# Clock_management.net
KiCad netlist of a schematic drawn in Altium Designer
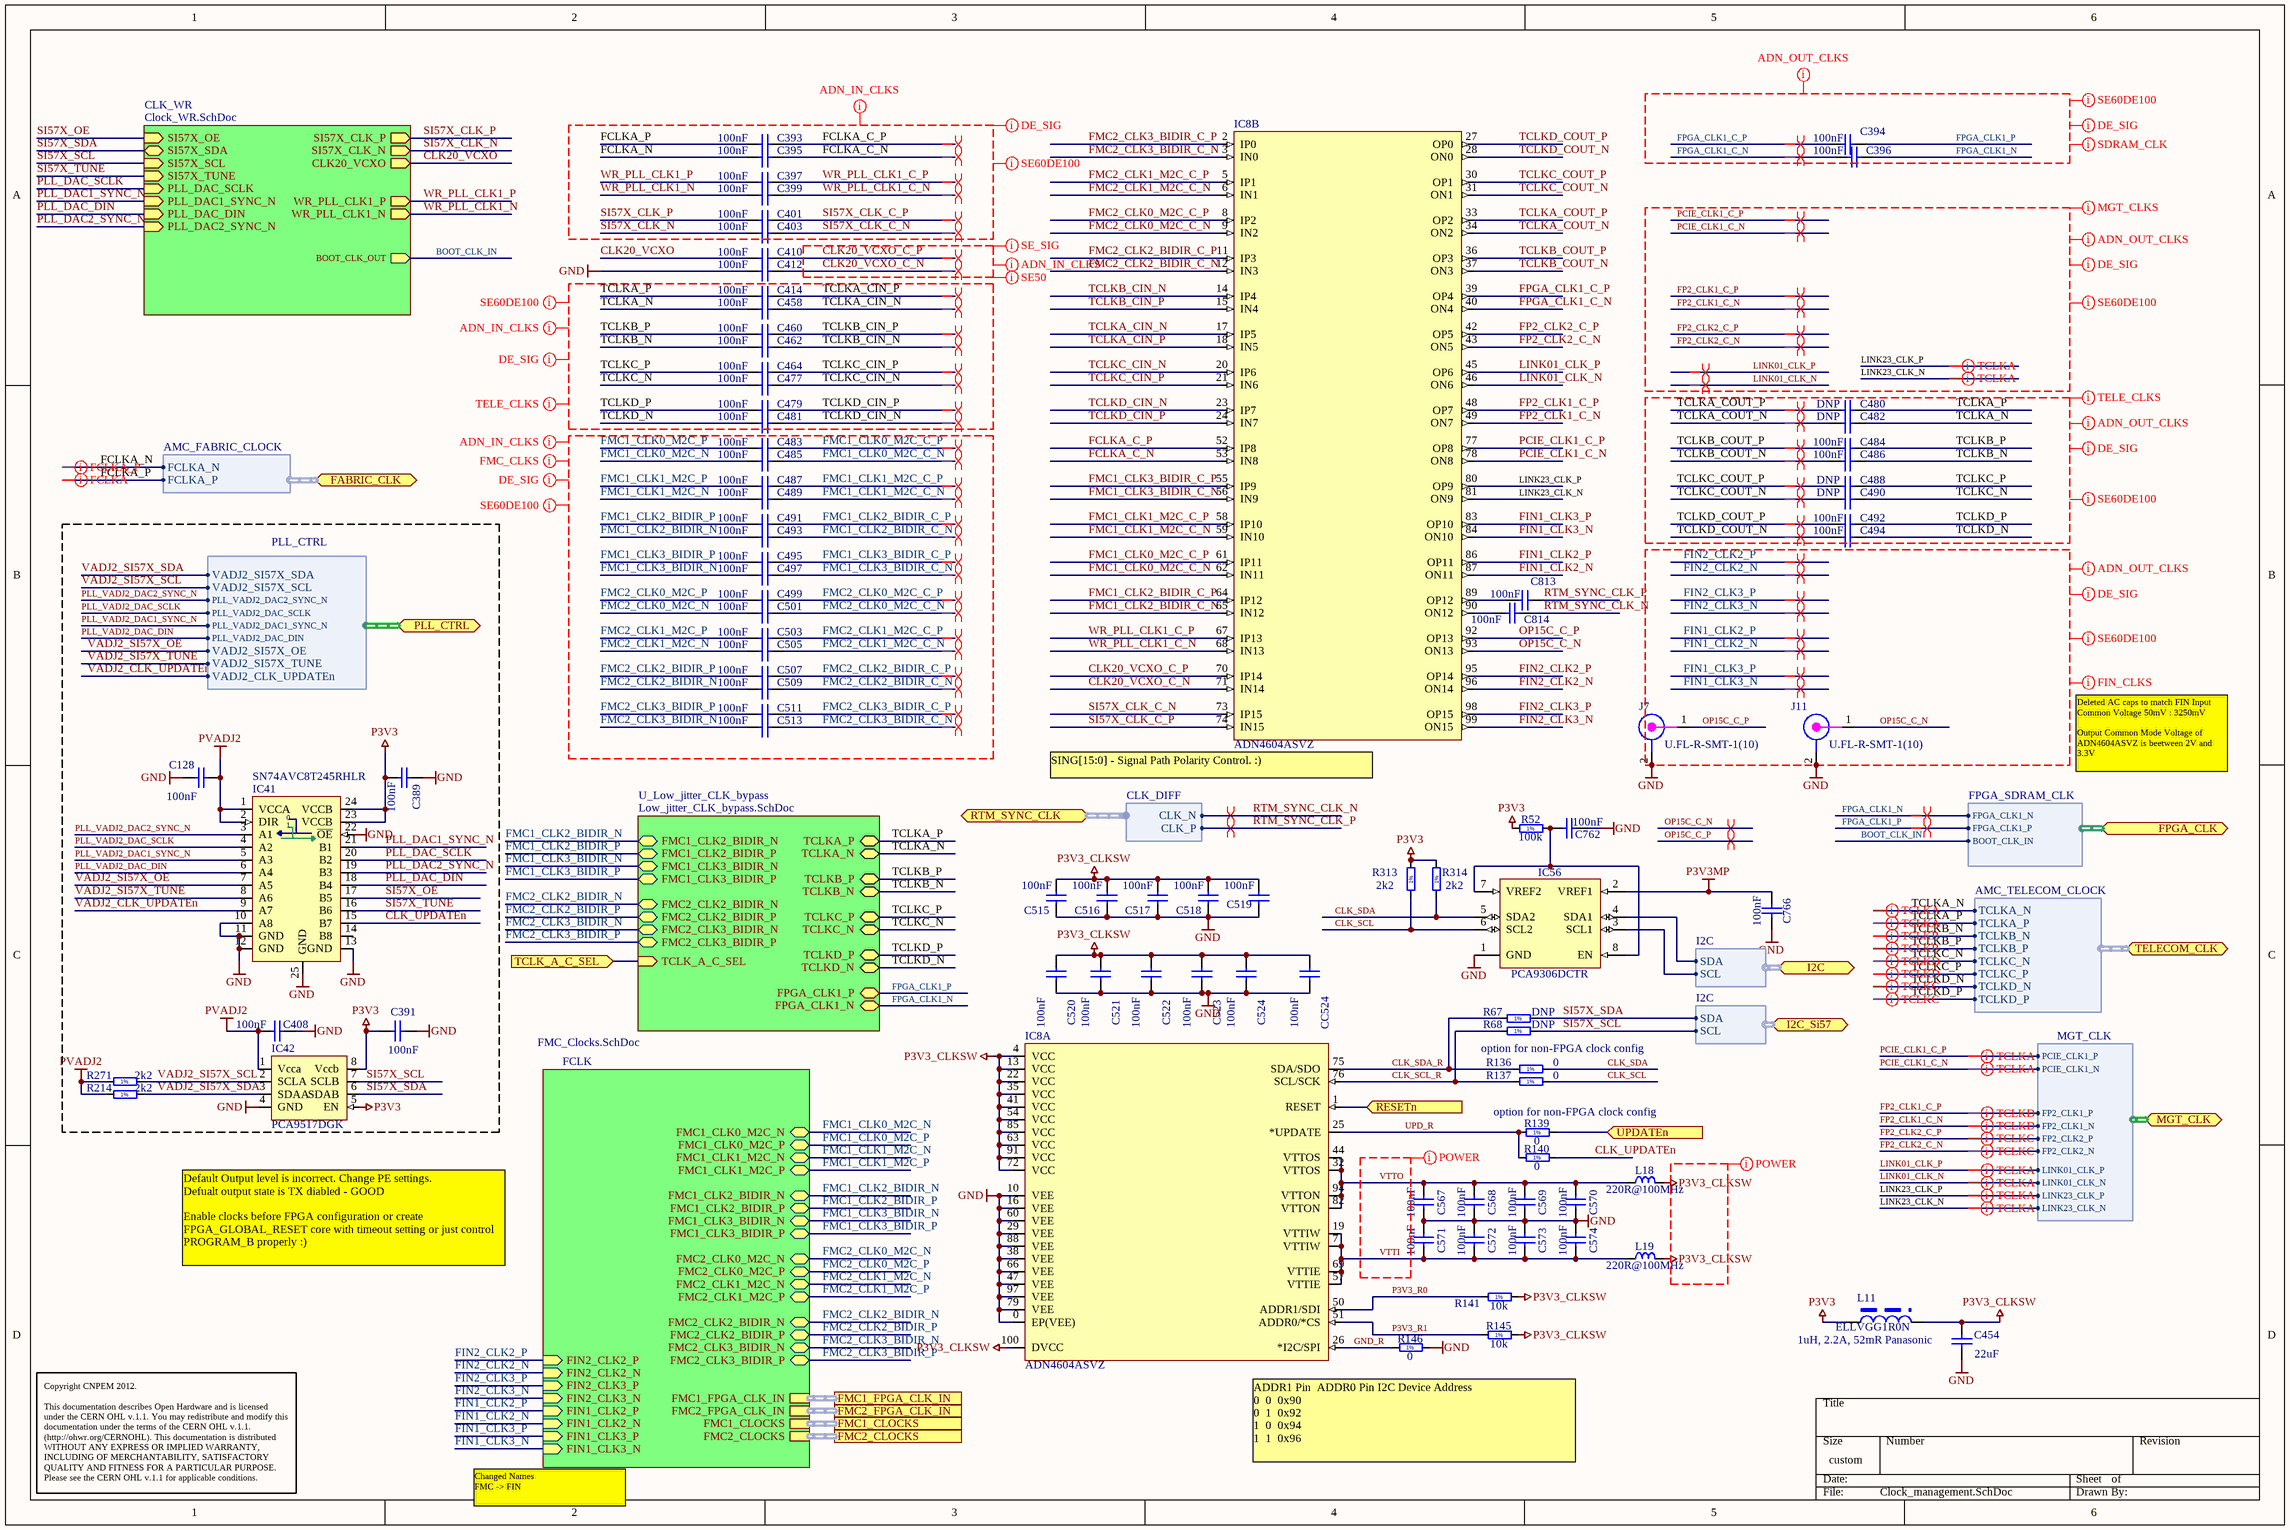
[diagram p0: Clock_management.SchDoc]

(export (version "E")
  (design (tool "Eeschema 10.0.6"))
  (components
    (comp (ref "C128")
      (value "100nF")
      (footprint "CAPC0603X33N")
      (description "Non-polarised capacitor")
      (fields
        (field (name "PART NUMBER") "CC0201_100NF_6.3V_10%_X5R")
        (field (name "VOLTAGE") "6.3V")
        (field (name "AUTHOR") "CERN DEM JLC")
      )
      (libsource (lib "Capacitors") (part "Capacitor - non polarized"))
    )
    (comp (ref "C389")
      (value "100nF")
      (footprint "CAPC0603X33N")
      (description "Non-polarised capacitor")
      (fields
        (field (name "PART NUMBER") "CC0201_100NF_6.3V_10%_X5R")
        (field (name "VOLTAGE") "6.3V")
        (field (name "AUTHOR") "CERN DEM JLC")
      )
      (libsource (lib "Capacitors") (part "Capacitor - non polarized"))
    )
    (comp (ref "C391")
      (value "100nF")
      (footprint "CAPC0603X33N")
      (description "Non-polarised capacitor")
      (fields
        (field (name "PART NUMBER") "CC0201_100NF_6.3V_10%_X5R")
        (field (name "VOLTAGE") "6.3V")
        (field (name "AUTHOR") "CERN DEM JLC")
      )
      (libsource (lib "Capacitors") (part "Capacitor - non polarized"))
    )
    (comp (ref "C393")
      (value "100nF")
      (footprint "CAPC0603X33N")
      (description "Non-polarised capacitor")
      (fields
        (field (name "PART NUMBER") "CC0201_100NF_6.3V_10%_X5R")
        (field (name "VOLTAGE") "6.3V")
        (field (name "AUTHOR") "CERN DEM JLC")
      )
      (libsource (lib "Capacitors") (part "Capacitor - non polarized"))
    )
    (comp (ref "C394")
      (value "100nF")
      (footprint "CAPC0603X33N")
      (description "Non-polarised capacitor")
      (fields
        (field (name "PART NUMBER") "CC0201_100NF_6.3V_10%_X5R")
        (field (name "VOLTAGE") "6.3V")
        (field (name "AUTHOR") "CERN DEM JLC")
      )
      (libsource (lib "Capacitors") (part "Capacitor - non polarized"))
    )
    (comp (ref "C395")
      (value "100nF")
      (footprint "CAPC0603X33N")
      (description "Non-polarised capacitor")
      (fields
        (field (name "PART NUMBER") "CC0201_100NF_6.3V_10%_X5R")
        (field (name "VOLTAGE") "6.3V")
        (field (name "AUTHOR") "CERN DEM JLC")
      )
      (libsource (lib "Capacitors") (part "Capacitor - non polarized"))
    )
    (comp (ref "C396")
      (value "100nF")
      (footprint "CAPC0603X33N")
      (description "Non-polarised capacitor")
      (fields
        (field (name "PART NUMBER") "CC0201_100NF_6.3V_10%_X5R")
        (field (name "VOLTAGE") "6.3V")
        (field (name "AUTHOR") "CERN DEM JLC")
      )
      (libsource (lib "Capacitors") (part "Capacitor - non polarized"))
    )
    (comp (ref "C397")
      (value "100nF")
      (footprint "CAPC0603X33N")
      (description "Non-polarised capacitor")
      (fields
        (field (name "PART NUMBER") "CC0201_100NF_6.3V_10%_X5R")
        (field (name "VOLTAGE") "6.3V")
        (field (name "AUTHOR") "CERN DEM JLC")
      )
      (libsource (lib "Capacitors") (part "Capacitor - non polarized"))
    )
    (comp (ref "C399")
      (value "100nF")
      (footprint "CAPC0603X33N")
      (description "Non-polarised capacitor")
      (fields
        (field (name "PART NUMBER") "CC0201_100NF_6.3V_10%_X5R")
        (field (name "VOLTAGE") "6.3V")
        (field (name "AUTHOR") "CERN DEM JLC")
      )
      (libsource (lib "Capacitors") (part "Capacitor - non polarized"))
    )
    (comp (ref "C401")
      (value "100nF")
      (footprint "CAPC0603X33N")
      (description "Non-polarised capacitor")
      (fields
        (field (name "PART NUMBER") "CC0201_100NF_6.3V_10%_X5R")
        (field (name "VOLTAGE") "6.3V")
        (field (name "AUTHOR") "CERN DEM JLC")
      )
      (libsource (lib "Capacitors") (part "Capacitor - non polarized"))
    )
    (comp (ref "C403")
      (value "100nF")
      (footprint "CAPC0603X33N")
      (description "Non-polarised capacitor")
      (fields
        (field (name "PART NUMBER") "CC0201_100NF_6.3V_10%_X5R")
        (field (name "VOLTAGE") "6.3V")
        (field (name "AUTHOR") "CERN DEM JLC")
      )
      (libsource (lib "Capacitors") (part "Capacitor - non polarized"))
    )
    (comp (ref "C408")
      (value "100nF")
      (footprint "CAPC0603X33N")
      (description "Non-polarised capacitor")
      (fields
        (field (name "PART NUMBER") "CC0201_100NF_6.3V_10%_X5R")
        (field (name "VOLTAGE") "6.3V")
        (field (name "AUTHOR") "CERN DEM JLC")
      )
      (libsource (lib "Capacitors") (part "Capacitor - non polarized"))
    )
    (comp (ref "C410")
      (value "100nF")
      (footprint "CAPC0603X33N")
      (description "Non-polarised capacitor")
      (fields
        (field (name "PART NUMBER") "CC0201_100NF_6.3V_10%_X5R")
        (field (name "VOLTAGE") "6.3V")
        (field (name "AUTHOR") "CERN DEM JLC")
      )
      (libsource (lib "Capacitors") (part "Capacitor - non polarized"))
    )
    (comp (ref "C412")
      (value "100nF")
      (footprint "CAPC0603X33N")
      (description "Non-polarised capacitor")
      (fields
        (field (name "PART NUMBER") "CC0201_100NF_6.3V_10%_X5R")
        (field (name "VOLTAGE") "6.3V")
        (field (name "AUTHOR") "CERN DEM JLC")
      )
      (libsource (lib "Capacitors") (part "Capacitor - non polarized"))
    )
    (comp (ref "C414")
      (value "100nF")
      (footprint "CAPC0603X33N")
      (description "Non-polarised capacitor")
      (fields
        (field (name "PART NUMBER") "CC0201_100NF_6.3V_10%_X5R")
        (field (name "VOLTAGE") "6.3V")
        (field (name "AUTHOR") "CERN DEM JLC")
      )
      (libsource (lib "Capacitors") (part "Capacitor - non polarized"))
    )
    (comp (ref "C454")
      (value "22uF")
      (footprint "CAPC3216X180N")
      (description "Non-polarised capacitor")
      (fields
        (field (name "PART NUMBER") "CC1206_22UF_10V_10%_X7R")
        (field (name "VOLTAGE") "10V")
        (field (name "AUTHOR") "CERN DEM JLC")
      )
      (libsource (lib "Capacitors") (part "Capacitor - non polarized"))
    )
    (comp (ref "C458")
      (value "100nF")
      (footprint "CAPC0603X33N")
      (description "Non-polarised capacitor")
      (fields
        (field (name "PART NUMBER") "CC0201_100NF_6.3V_10%_X5R")
        (field (name "VOLTAGE") "6.3V")
        (field (name "AUTHOR") "CERN DEM JLC")
      )
      (libsource (lib "Capacitors") (part "Capacitor - non polarized"))
    )
    (comp (ref "C460")
      (value "100nF")
      (footprint "CAPC0603X33N")
      (description "Non-polarised capacitor")
      (fields
        (field (name "PART NUMBER") "CC0201_100NF_6.3V_10%_X5R")
        (field (name "VOLTAGE") "6.3V")
        (field (name "AUTHOR") "CERN DEM JLC")
      )
      (libsource (lib "Capacitors") (part "Capacitor - non polarized"))
    )
    (comp (ref "C462")
      (value "100nF")
      (footprint "CAPC0603X33N")
      (description "Non-polarised capacitor")
      (fields
        (field (name "PART NUMBER") "CC0201_100NF_6.3V_10%_X5R")
        (field (name "VOLTAGE") "6.3V")
        (field (name "AUTHOR") "CERN DEM JLC")
      )
      (libsource (lib "Capacitors") (part "Capacitor - non polarized"))
    )
    (comp (ref "C464")
      (value "100nF")
      (footprint "CAPC0603X33N")
      (description "Non-polarised capacitor")
      (fields
        (field (name "PART NUMBER") "CC0201_100NF_6.3V_10%_X5R")
        (field (name "VOLTAGE") "6.3V")
        (field (name "AUTHOR") "CERN DEM JLC")
      )
      (libsource (lib "Capacitors") (part "Capacitor - non polarized"))
    )
    (comp (ref "C477")
      (value "100nF")
      (footprint "CAPC0603X33N")
      (description "Non-polarised capacitor")
      (fields
        (field (name "PART NUMBER") "CC0201_100NF_6.3V_10%_X5R")
        (field (name "VOLTAGE") "6.3V")
        (field (name "AUTHOR") "CERN DEM JLC")
      )
      (libsource (lib "Capacitors") (part "Capacitor - non polarized"))
    )
    (comp (ref "C479")
      (value "100nF")
      (footprint "CAPC0603X33N")
      (description "Non-polarised capacitor")
      (fields
        (field (name "PART NUMBER") "CC0201_100NF_6.3V_10%_X5R")
        (field (name "VOLTAGE") "6.3V")
        (field (name "AUTHOR") "CERN DEM JLC")
      )
      (libsource (lib "Capacitors") (part "Capacitor - non polarized"))
    )
    (comp (ref "C480")
      (value "DNP")
      (footprint "CAPC0603X33N")
      (description "Non-polarised capacitor")
      (fields
        (field (name "PART NUMBER") "CC0201_100NF_6.3V_10%_X5R")
        (field (name "VOLTAGE") "6.3V")
        (field (name "AUTHOR") "CERN DEM JLC")
      )
      (libsource (lib "Capacitors") (part "Capacitor - non polarized"))
    )
    (comp (ref "C481")
      (value "100nF")
      (footprint "CAPC0603X33N")
      (description "Non-polarised capacitor")
      (fields
        (field (name "PART NUMBER") "CC0201_100NF_6.3V_10%_X5R")
        (field (name "VOLTAGE") "6.3V")
        (field (name "AUTHOR") "CERN DEM JLC")
      )
      (libsource (lib "Capacitors") (part "Capacitor - non polarized"))
    )
    (comp (ref "C482")
      (value "DNP")
      (footprint "CAPC0603X33N")
      (description "Non-polarised capacitor")
      (fields
        (field (name "PART NUMBER") "CC0201_100NF_6.3V_10%_X5R")
        (field (name "VOLTAGE") "6.3V")
        (field (name "AUTHOR") "CERN DEM JLC")
      )
      (libsource (lib "Capacitors") (part "Capacitor - non polarized"))
    )
    (comp (ref "C483")
      (value "100nF")
      (footprint "CAPC0603X33N")
      (description "Non-polarised capacitor")
      (fields
        (field (name "PART NUMBER") "CC0201_100NF_6.3V_10%_X5R")
        (field (name "VOLTAGE") "6.3V")
        (field (name "AUTHOR") "CERN DEM JLC")
      )
      (libsource (lib "Capacitors") (part "Capacitor - non polarized"))
    )
    (comp (ref "C484")
      (value "100nF")
      (footprint "CAPC0603X33N")
      (description "Non-polarised capacitor")
      (fields
        (field (name "PART NUMBER") "CC0201_100NF_6.3V_10%_X5R")
        (field (name "VOLTAGE") "6.3V")
        (field (name "AUTHOR") "CERN DEM JLC")
      )
      (libsource (lib "Capacitors") (part "Capacitor - non polarized"))
    )
    (comp (ref "C485")
      (value "100nF")
      (footprint "CAPC0603X33N")
      (description "Non-polarised capacitor")
      (fields
        (field (name "PART NUMBER") "CC0201_100NF_6.3V_10%_X5R")
        (field (name "VOLTAGE") "6.3V")
        (field (name "AUTHOR") "CERN DEM JLC")
      )
      (libsource (lib "Capacitors") (part "Capacitor - non polarized"))
    )
    (comp (ref "C486")
      (value "100nF")
      (footprint "CAPC0603X33N")
      (description "Non-polarised capacitor")
      (fields
        (field (name "PART NUMBER") "CC0201_100NF_6.3V_10%_X5R")
        (field (name "VOLTAGE") "6.3V")
        (field (name "AUTHOR") "CERN DEM JLC")
      )
      (libsource (lib "Capacitors") (part "Capacitor - non polarized"))
    )
    (comp (ref "C487")
      (value "100nF")
      (footprint "CAPC0603X33N")
      (description "Non-polarised capacitor")
      (fields
        (field (name "PART NUMBER") "CC0201_100NF_6.3V_10%_X5R")
        (field (name "VOLTAGE") "6.3V")
        (field (name "AUTHOR") "CERN DEM JLC")
      )
      (libsource (lib "Capacitors") (part "Capacitor - non polarized"))
    )
    (comp (ref "C488")
      (value "DNP")
      (footprint "CAPC0603X33N")
      (description "Non-polarised capacitor")
      (fields
        (field (name "PART NUMBER") "CC0201_100NF_6.3V_10%_X5R")
        (field (name "VOLTAGE") "6.3V")
        (field (name "AUTHOR") "CERN DEM JLC")
      )
      (libsource (lib "Capacitors") (part "Capacitor - non polarized"))
    )
    (comp (ref "C489")
      (value "100nF")
      (footprint "CAPC0603X33N")
      (description "Non-polarised capacitor")
      (fields
        (field (name "PART NUMBER") "CC0201_100NF_6.3V_10%_X5R")
        (field (name "VOLTAGE") "6.3V")
        (field (name "AUTHOR") "CERN DEM JLC")
      )
      (libsource (lib "Capacitors") (part "Capacitor - non polarized"))
    )
    (comp (ref "C490")
      (value "DNP")
      (footprint "CAPC0603X33N")
      (description "Non-polarised capacitor")
      (fields
        (field (name "PART NUMBER") "CC0201_100NF_6.3V_10%_X5R")
        (field (name "VOLTAGE") "6.3V")
        (field (name "AUTHOR") "CERN DEM JLC")
      )
      (libsource (lib "Capacitors") (part "Capacitor - non polarized"))
    )
    (comp (ref "C491")
      (value "100nF")
      (footprint "CAPC0603X33N")
      (description "Non-polarised capacitor")
      (fields
        (field (name "PART NUMBER") "CC0201_100NF_6.3V_10%_X5R")
        (field (name "VOLTAGE") "6.3V")
        (field (name "AUTHOR") "CERN DEM JLC")
      )
      (libsource (lib "Capacitors") (part "Capacitor - non polarized"))
    )
    (comp (ref "C492")
      (value "100nF")
      (footprint "CAPC0603X33N")
      (description "Non-polarised capacitor")
      (fields
        (field (name "PART NUMBER") "CC0201_100NF_6.3V_10%_X5R")
        (field (name "VOLTAGE") "6.3V")
        (field (name "AUTHOR") "CERN DEM JLC")
      )
      (libsource (lib "Capacitors") (part "Capacitor - non polarized"))
    )
    (comp (ref "C493")
      (value "100nF")
      (footprint "CAPC0603X33N")
      (description "Non-polarised capacitor")
      (fields
        (field (name "PART NUMBER") "CC0201_100NF_6.3V_10%_X5R")
        (field (name "VOLTAGE") "6.3V")
        (field (name "AUTHOR") "CERN DEM JLC")
      )
      (libsource (lib "Capacitors") (part "Capacitor - non polarized"))
    )
    (comp (ref "C494")
      (value "100nF")
      (footprint "CAPC0603X33N")
      (description "Non-polarised capacitor")
      (fields
        (field (name "PART NUMBER") "CC0201_100NF_6.3V_10%_X5R")
        (field (name "VOLTAGE") "6.3V")
        (field (name "AUTHOR") "CERN DEM JLC")
      )
      (libsource (lib "Capacitors") (part "Capacitor - non polarized"))
    )
    (comp (ref "C495")
      (value "100nF")
      (footprint "CAPC0603X33N")
      (description "Non-polarised capacitor")
      (fields
        (field (name "PART NUMBER") "CC0201_100NF_6.3V_10%_X5R")
        (field (name "VOLTAGE") "6.3V")
        (field (name "AUTHOR") "CERN DEM JLC")
      )
      (libsource (lib "Capacitors") (part "Capacitor - non polarized"))
    )
    (comp (ref "C497")
      (value "100nF")
      (footprint "CAPC0603X33N")
      (description "Non-polarised capacitor")
      (fields
        (field (name "PART NUMBER") "CC0201_100NF_6.3V_10%_X5R")
        (field (name "VOLTAGE") "6.3V")
        (field (name "AUTHOR") "CERN DEM JLC")
      )
      (libsource (lib "Capacitors") (part "Capacitor - non polarized"))
    )
    (comp (ref "C499")
      (value "100nF")
      (footprint "CAPC0603X33N")
      (description "Non-polarised capacitor")
      (fields
        (field (name "PART NUMBER") "CC0201_100NF_6.3V_10%_X5R")
        (field (name "VOLTAGE") "6.3V")
        (field (name "AUTHOR") "CERN DEM JLC")
      )
      (libsource (lib "Capacitors") (part "Capacitor - non polarized"))
    )
    (comp (ref "C501")
      (value "100nF")
      (footprint "CAPC0603X33N")
      (description "Non-polarised capacitor")
      (fields
        (field (name "PART NUMBER") "CC0201_100NF_6.3V_10%_X5R")
        (field (name "VOLTAGE") "6.3V")
        (field (name "AUTHOR") "CERN DEM JLC")
      )
      (libsource (lib "Capacitors") (part "Capacitor - non polarized"))
    )
    (comp (ref "C503")
      (value "100nF")
      (footprint "CAPC0603X33N")
      (description "Non-polarised capacitor")
      (fields
        (field (name "PART NUMBER") "CC0201_100NF_6.3V_10%_X5R")
        (field (name "VOLTAGE") "6.3V")
        (field (name "AUTHOR") "CERN DEM JLC")
      )
      (libsource (lib "Capacitors") (part "Capacitor - non polarized"))
    )
    (comp (ref "C505")
      (value "100nF")
      (footprint "CAPC0603X33N")
      (description "Non-polarised capacitor")
      (fields
        (field (name "PART NUMBER") "CC0201_100NF_6.3V_10%_X5R")
        (field (name "VOLTAGE") "6.3V")
        (field (name "AUTHOR") "CERN DEM JLC")
      )
      (libsource (lib "Capacitors") (part "Capacitor - non polarized"))
    )
    (comp (ref "C507")
      (value "100nF")
      (footprint "CAPC0603X33N")
      (description "Non-polarised capacitor")
      (fields
        (field (name "PART NUMBER") "CC0201_100NF_6.3V_10%_X5R")
        (field (name "VOLTAGE") "6.3V")
        (field (name "AUTHOR") "CERN DEM JLC")
      )
      (libsource (lib "Capacitors") (part "Capacitor - non polarized"))
    )
    (comp (ref "C509")
      (value "100nF")
      (footprint "CAPC0603X33N")
      (description "Non-polarised capacitor")
      (fields
        (field (name "PART NUMBER") "CC0201_100NF_6.3V_10%_X5R")
        (field (name "VOLTAGE") "6.3V")
        (field (name "AUTHOR") "CERN DEM JLC")
      )
      (libsource (lib "Capacitors") (part "Capacitor - non polarized"))
    )
    (comp (ref "C511")
      (value "100nF")
      (footprint "CAPC0603X33N")
      (description "Non-polarised capacitor")
      (fields
        (field (name "PART NUMBER") "CC0201_100NF_6.3V_10%_X5R")
        (field (name "VOLTAGE") "6.3V")
        (field (name "AUTHOR") "CERN DEM JLC")
      )
      (libsource (lib "Capacitors") (part "Capacitor - non polarized"))
    )
    (comp (ref "C513")
      (value "100nF")
      (footprint "CAPC0603X33N")
      (description "Non-polarised capacitor")
      (fields
        (field (name "PART NUMBER") "CC0201_100NF_6.3V_10%_X5R")
        (field (name "VOLTAGE") "6.3V")
        (field (name "AUTHOR") "CERN DEM JLC")
      )
      (libsource (lib "Capacitors") (part "Capacitor - non polarized"))
    )
    (comp (ref "C515")
      (value "100nF")
      (footprint "CAPC0603X33N")
      (description "Non-polarised capacitor")
      (fields
        (field (name "PART NUMBER") "CC0201_100NF_6.3V_10%_X5R")
        (field (name "VOLTAGE") "6.3V")
        (field (name "AUTHOR") "CERN DEM JLC")
      )
      (libsource (lib "Capacitors") (part "Capacitor - non polarized"))
    )
    (comp (ref "C516")
      (value "100nF")
      (footprint "CAPC0603X33N")
      (description "Non-polarised capacitor")
      (fields
        (field (name "PART NUMBER") "CC0201_100NF_6.3V_10%_X5R")
        (field (name "VOLTAGE") "6.3V")
        (field (name "AUTHOR") "CERN DEM JLC")
      )
      (libsource (lib "Capacitors") (part "Capacitor - non polarized"))
    )
    (comp (ref "C517")
      (value "100nF")
      (footprint "CAPC0603X33N")
      (description "Non-polarised capacitor")
      (fields
        (field (name "PART NUMBER") "CC0201_100NF_6.3V_10%_X5R")
        (field (name "VOLTAGE") "6.3V")
        (field (name "AUTHOR") "CERN DEM JLC")
      )
      (libsource (lib "Capacitors") (part "Capacitor - non polarized"))
    )
    (comp (ref "C518")
      (value "100nF")
      (footprint "CAPC0603X33N")
      (description "Non-polarised capacitor")
      (fields
        (field (name "PART NUMBER") "CC0201_100NF_6.3V_10%_X5R")
        (field (name "VOLTAGE") "6.3V")
        (field (name "AUTHOR") "CERN DEM JLC")
      )
      (libsource (lib "Capacitors") (part "Capacitor - non polarized"))
    )
    (comp (ref "C519")
      (value "100nF")
      (footprint "CAPC0603X33N")
      (description "Non-polarised capacitor")
      (fields
        (field (name "PART NUMBER") "CC0201_100NF_6.3V_10%_X5R")
        (field (name "VOLTAGE") "6.3V")
        (field (name "AUTHOR") "CERN DEM JLC")
      )
      (libsource (lib "Capacitors") (part "Capacitor - non polarized"))
    )
    (comp (ref "C520")
      (value "100nF")
      (footprint "CAPC0603X33N")
      (description "Non-polarised capacitor")
      (fields
        (field (name "PART NUMBER") "CC0201_100NF_6.3V_10%_X5R")
        (field (name "VOLTAGE") "6.3V")
        (field (name "AUTHOR") "CERN DEM JLC")
      )
      (libsource (lib "Capacitors") (part "Capacitor - non polarized"))
    )
    (comp (ref "C521")
      (value "100nF")
      (footprint "CAPC0603X33N")
      (description "Non-polarised capacitor")
      (fields
        (field (name "PART NUMBER") "CC0201_100NF_6.3V_10%_X5R")
        (field (name "VOLTAGE") "6.3V")
        (field (name "AUTHOR") "CERN DEM JLC")
      )
      (libsource (lib "Capacitors") (part "Capacitor - non polarized"))
    )
    (comp (ref "C522")
      (value "100nF")
      (footprint "CAPC0603X33N")
      (description "Non-polarised capacitor")
      (fields
        (field (name "PART NUMBER") "CC0201_100NF_6.3V_10%_X5R")
        (field (name "VOLTAGE") "6.3V")
        (field (name "AUTHOR") "CERN DEM JLC")
      )
      (libsource (lib "Capacitors") (part "Capacitor - non polarized"))
    )
    (comp (ref "C523")
      (value "100nF")
      (footprint "CAPC0603X33N")
      (description "Non-polarised capacitor")
      (fields
        (field (name "PART NUMBER") "CC0201_100NF_6.3V_10%_X5R")
        (field (name "VOLTAGE") "6.3V")
        (field (name "AUTHOR") "CERN DEM JLC")
      )
      (libsource (lib "Capacitors") (part "Capacitor - non polarized"))
    )
    (comp (ref "C524")
      (value "100nF")
      (footprint "CAPC0603X33N")
      (description "Non-polarised capacitor")
      (fields
        (field (name "PART NUMBER") "CC0201_100NF_6.3V_10%_X5R")
        (field (name "VOLTAGE") "6.3V")
        (field (name "AUTHOR") "CERN DEM JLC")
      )
      (libsource (lib "Capacitors") (part "Capacitor - non polarized"))
    )
    (comp (ref "C567")
      (value "100nF")
      (footprint "CAPC0603X33N")
      (description "Non-polarised capacitor")
      (fields
        (field (name "PART NUMBER") "CC0201_100NF_6.3V_10%_X5R")
        (field (name "VOLTAGE") "6.3V")
        (field (name "AUTHOR") "CERN DEM JLC")
      )
      (libsource (lib "Capacitors") (part "Capacitor - non polarized"))
    )
    (comp (ref "C568")
      (value "100nF")
      (footprint "CAPC0603X33N")
      (description "Non-polarised capacitor")
      (fields
        (field (name "PART NUMBER") "CC0201_100NF_6.3V_10%_X5R")
        (field (name "VOLTAGE") "6.3V")
        (field (name "AUTHOR") "CERN DEM JLC")
      )
      (libsource (lib "Capacitors") (part "Capacitor - non polarized"))
    )
    (comp (ref "C569")
      (value "100nF")
      (footprint "CAPC0603X33N")
      (description "Non-polarised capacitor")
      (fields
        (field (name "PART NUMBER") "CC0201_100NF_6.3V_10%_X5R")
        (field (name "VOLTAGE") "6.3V")
        (field (name "AUTHOR") "CERN DEM JLC")
      )
      (libsource (lib "Capacitors") (part "Capacitor - non polarized"))
    )
    (comp (ref "C570")
      (value "100nF")
      (footprint "CAPC0603X33N")
      (description "Non-polarised capacitor")
      (fields
        (field (name "PART NUMBER") "CC0201_100NF_6.3V_10%_X5R")
        (field (name "VOLTAGE") "6.3V")
        (field (name "AUTHOR") "CERN DEM JLC")
      )
      (libsource (lib "Capacitors") (part "Capacitor - non polarized"))
    )
    (comp (ref "C571")
      (value "100nF")
      (footprint "CAPC0603X33N")
      (description "Non-polarised capacitor")
      (fields
        (field (name "PART NUMBER") "CC0201_100NF_6.3V_10%_X5R")
        (field (name "VOLTAGE") "6.3V")
        (field (name "AUTHOR") "CERN DEM JLC")
      )
      (libsource (lib "Capacitors") (part "Capacitor - non polarized"))
    )
    (comp (ref "C572")
      (value "100nF")
      (footprint "CAPC0603X33N")
      (description "Non-polarised capacitor")
      (fields
        (field (name "PART NUMBER") "CC0201_100NF_6.3V_10%_X5R")
        (field (name "VOLTAGE") "6.3V")
        (field (name "AUTHOR") "CERN DEM JLC")
      )
      (libsource (lib "Capacitors") (part "Capacitor - non polarized"))
    )
    (comp (ref "C573")
      (value "100nF")
      (footprint "CAPC0603X33N")
      (description "Non-polarised capacitor")
      (fields
        (field (name "PART NUMBER") "CC0201_100NF_6.3V_10%_X5R")
        (field (name "VOLTAGE") "6.3V")
        (field (name "AUTHOR") "CERN DEM JLC")
      )
      (libsource (lib "Capacitors") (part "Capacitor - non polarized"))
    )
    (comp (ref "C574")
      (value "100nF")
      (footprint "CAPC0603X33N")
      (description "Non-polarised capacitor")
      (fields
        (field (name "PART NUMBER") "CC0201_100NF_6.3V_10%_X5R")
        (field (name "VOLTAGE") "6.3V")
        (field (name "AUTHOR") "CERN DEM JLC")
      )
      (libsource (lib "Capacitors") (part "Capacitor - non polarized"))
    )
    (comp (ref "C762")
      (value "100nF")
      (footprint "CAPC0603X33N")
      (description "Non-polarised capacitor")
      (fields
        (field (name "PART NUMBER") "CC0201_100NF_6.3V_10%_X5R")
        (field (name "VOLTAGE") "6.3V")
        (field (name "AUTHOR") "CERN DEM JLC")
      )
      (libsource (lib "Capacitors") (part "Capacitor - non polarized"))
    )
    (comp (ref "C766")
      (value "100nF")
      (footprint "CAPC0603X33N")
      (description "Non-polarised capacitor")
      (fields
        (field (name "PART NUMBER") "CC0201_100NF_6.3V_10%_X5R")
        (field (name "VOLTAGE") "6.3V")
        (field (name "AUTHOR") "CERN DEM JLC")
      )
      (libsource (lib "Capacitors") (part "Capacitor - non polarized"))
    )
    (comp (ref "C813")
      (value "100nF")
      (footprint "CAPC0603X33N")
      (description "Non-polarised capacitor")
      (fields
        (field (name "PART NUMBER") "CC0201_100NF_6.3V_10%_X5R")
        (field (name "VOLTAGE") "6.3V")
        (field (name "AUTHOR") "CERN DEM JLC")
      )
      (libsource (lib "Capacitors") (part "Capacitor - non polarized"))
    )
    (comp (ref "C814")
      (value "100nF")
      (footprint "CAPC0603X33N")
      (description "Non-polarised capacitor")
      (fields
        (field (name "PART NUMBER") "CC0201_100NF_6.3V_10%_X5R")
        (field (name "VOLTAGE") "6.3V")
        (field (name "AUTHOR") "CERN DEM JLC")
      )
      (libsource (lib "Capacitors") (part "Capacitor - non polarized"))
    )
    (comp (ref "CC524")
      (value "100nF")
      (footprint "CAPC0603X33N")
      (description "Non-polarised capacitor")
      (fields
        (field (name "PART NUMBER") "CC0201_100NF_6.3V_10%_X5R")
        (field (name "VOLTAGE") "6.3V")
        (field (name "AUTHOR") "CERN DEM JLC")
      )
      (libsource (lib "Capacitors") (part "Capacitor - non polarized"))
    )
    (comp (ref "IC8")
      (value "ADN4604ASVZ")
      (footprint "TQFP100_TP")
      (description "16x16 CML crosspoint switch")
      (libsource (lib "LIBRARY_SCH") (part "IFC_ADN4604ASVZ"))
    )
    (comp (ref "IC41")
      (value "SN74AVC8T245RHLR")
      (footprint "QFN50P350X550X100-24N")
      (description "8 channel bidir translator buffer (1.4..3.6V)")
      (libsource (lib "LIBRARY_SCH") (part "74AVC8T245_QFN"))
    )
    (comp (ref "IC42")
      (value "PCA9517DGK")
      (footprint "msop-8")
      (description "LEVEL-TRANSLATING I2C BUS REPEATER")
      (libsource (lib "LIBRARY_SCH") (part "IFC_PCA9517"))
    )
    (comp (ref "IC56")
      (value "PCA9306DCTR")
      (footprint "SOP65P400X130-8N")
      (description "Dual Bidirectional I2C Bus And SMBus Voltage-Level Translator")
      (fields (field (name "MANUFACTURER") "TEXAS INSTRUMENTS") (field (name "AUTHOR") "CERN DEM JLC"))
      (libsource (lib "ICs And Semiconductors") (part "PCA9306DC"))
    )
    (comp (ref "J7")
      (value "U.FL-R-SMT-1(10)")
      (footprint "CON_UFL_HIROSE_RECEPTACLE")
      (description "UFL")
      (libsource (lib "LIBRARY_SCH") (part "CON_UFL_SMD"))
    )
    (comp (ref "J11")
      (value "U.FL-R-SMT-1(10)")
      (footprint "CON_UFL_HIROSE_RECEPTACLE")
      (description "UFL")
      (libsource (lib "LIBRARY_SCH") (part "CON_UFL_SMD"))
    )
    (comp (ref "L11")
      (value "ELLVGG1R0N")
      (footprint "L_ELLVGG2R2N")
      (description "2.2uH, 1.4A, 92mR Panasonic")
      (fields (field (name "ALTIUM_UNNAMED_1") "1uH, 2.2A, 52mR Panasonic"))
      (libsource (lib "LIBRARY_SCH") (part "L_CHOKE_ELLVGG"))
    )
    (comp (ref "L18")
      (value "220R@100MHz")
      (footprint "INDC2012X105N")
      (description "Inductor")
      (fields
        (field (name "PART NUMBER") "IND0805_MURATA_BLM21PG221SN1D")
        (field (name "POWER") "2A")
        (field (name "AUTHOR") "CERN DEM JLC")
      )
      (libsource (lib "Inductors & Transformers") (part "Inductor"))
    )
    (comp (ref "L19")
      (value "220R@100MHz")
      (footprint "INDC2012X105N")
      (description "Inductor")
      (fields
        (field (name "PART NUMBER") "IND0805_MURATA_BLM21PG221SN1D")
        (field (name "POWER") "2A")
        (field (name "AUTHOR") "CERN DEM JLC")
      )
      (libsource (lib "Inductors & Transformers") (part "Inductor"))
    )
    (comp (ref "R52")
      (value "100k")
      (footprint "RESC1005X40N")
      (description "Resistor - 1%")
      (fields
        (field (name "PART NUMBER") "R0402_100K_1%_0.0625W_100PPM")
        (field (name "POWER") "0.0625W")
        (field (name "AUTHOR") "CERN DEM JLC")
      )
      (libsource (lib "Resistors") (part "Resistor - 1%"))
    )
    (comp (ref "R67")
      (value "DNP")
      (footprint "RESC1005X40N")
      (description "Resistor - 1%")
      (fields
        (field (name "PART NUMBER") "R0402_0R_JUMPER")
        (field (name "MANUFACTURER") "GENERIC")
        (field (name "AUTHOR") "CERN DEM JLC")
      )
      (libsource (lib "Resistors") (part "Resistor - 1%"))
    )
    (comp (ref "R68")
      (value "DNP")
      (footprint "RESC1005X40N")
      (description "Resistor - 1%")
      (fields
        (field (name "PART NUMBER") "R0402_0R_JUMPER")
        (field (name "MANUFACTURER") "GENERIC")
        (field (name "AUTHOR") "CERN DEM JLC")
      )
      (libsource (lib "Resistors") (part "Resistor - 1%"))
    )
    (comp (ref "R136")
      (value "0")
      (footprint "RESC1005X40N")
      (description "Resistor - 1%")
      (fields
        (field (name "PART NUMBER") "R0402_0R_JUMPER")
        (field (name "MANUFACTURER") "GENERIC")
        (field (name "AUTHOR") "CERN DEM JLC")
      )
      (libsource (lib "Resistors") (part "Resistor - 1%"))
    )
    (comp (ref "R137")
      (value "0")
      (footprint "RESC1005X40N")
      (description "Resistor - 1%")
      (fields
        (field (name "PART NUMBER") "R0402_0R_JUMPER")
        (field (name "MANUFACTURER") "GENERIC")
        (field (name "AUTHOR") "CERN DEM JLC")
      )
      (libsource (lib "Resistors") (part "Resistor - 1%"))
    )
    (comp (ref "R139")
      (value "0")
      (footprint "RESC1005X40N")
      (description "Resistor - 1%")
      (fields
        (field (name "PART NUMBER") "R0402_0R_JUMPER")
        (field (name "MANUFACTURER") "GENERIC")
        (field (name "AUTHOR") "CERN DEM JLC")
      )
      (libsource (lib "Resistors") (part "Resistor - 1%"))
    )
    (comp (ref "R140")
      (value "0")
      (footprint "RESC1005X40N")
      (description "Resistor - 1%")
      (fields
        (field (name "PART NUMBER") "R0402_0R_JUMPER")
        (field (name "MANUFACTURER") "GENERIC")
        (field (name "AUTHOR") "CERN DEM JLC")
      )
      (libsource (lib "Resistors") (part "Resistor - 1%"))
    )
    (comp (ref "R141")
      (value "10k")
      (footprint "RESC1005X40N")
      (description "Resistor - 1%")
      (fields
        (field (name "PART NUMBER") "R0402_10K_1%_0.0625W_100PPM")
        (field (name "POWER") "0.0625W")
        (field (name "AUTHOR") "CERN DEM JLC")
      )
      (libsource (lib "Resistors") (part "Resistor - 1%"))
    )
    (comp (ref "R145")
      (value "10k")
      (footprint "RESC1005X40N")
      (description "Resistor - 1%")
      (fields
        (field (name "PART NUMBER") "R0402_10K_1%_0.0625W_100PPM")
        (field (name "POWER") "0.0625W")
        (field (name "AUTHOR") "CERN DEM JLC")
      )
      (libsource (lib "Resistors") (part "Resistor - 1%"))
    )
    (comp (ref "R146")
      (value "0")
      (footprint "RESC1005X40N")
      (description "Resistor - 1%")
      (fields
        (field (name "PART NUMBER") "R0402_0R_JUMPER")
        (field (name "MANUFACTURER") "GENERIC")
        (field (name "AUTHOR") "CERN DEM JLC")
      )
      (libsource (lib "Resistors") (part "Resistor - 1%"))
    )
    (comp (ref "R214")
      (value "2k2")
      (footprint "RESC1005X40N")
      (description "Resistor - 1%")
      (fields
        (field (name "PART NUMBER") "R0402_2K2_1%_0.0625W_100PPM")
        (field (name "POWER") "0.0625W")
        (field (name "AUTHOR") "CERN DEM JLC")
      )
      (libsource (lib "Resistors") (part "Resistor - 1%"))
    )
    (comp (ref "R271")
      (value "2k2")
      (footprint "RESC1005X40N")
      (description "Resistor - 1%")
      (fields
        (field (name "PART NUMBER") "R0402_2K2_1%_0.0625W_100PPM")
        (field (name "POWER") "0.0625W")
        (field (name "AUTHOR") "CERN DEM JLC")
      )
      (libsource (lib "Resistors") (part "Resistor - 1%"))
    )
    (comp (ref "R313")
      (value "2k2")
      (footprint "RESC1005X40N")
      (description "Resistor - 1%")
      (fields
        (field (name "PART NUMBER") "R0402_2K2_1%_0.0625W_100PPM")
        (field (name "POWER") "0.0625W")
        (field (name "AUTHOR") "CERN DEM JLC")
      )
      (libsource (lib "Resistors") (part "Resistor - 1%"))
    )
    (comp (ref "R314")
      (value "2k2")
      (footprint "RESC1005X40N")
      (description "Resistor - 1%")
      (fields
        (field (name "PART NUMBER") "R0402_2K2_1%_0.0625W_100PPM")
        (field (name "POWER") "0.0625W")
        (field (name "AUTHOR") "CERN DEM JLC")
      )
      (libsource (lib "Resistors") (part "Resistor - 1%"))
    )
  )
  (nets
    (net (code "13") (name "/CLK20_VCXO") (class "Default")
      (node (ref "C410") (pin "1") (pinfunction "1_1") (pintype "passive"))
    )
    (net (code "14") (name "/CLK20_VCXO_C_N") (class "Default")
      (node (ref "C412") (pin "2") (pinfunction "2_2") (pintype "passive"))
      (node (ref "IC8") (pin "71") (pinfunction "IN14_71") (pintype "input"))
    )
    (net (code "15") (name "/CLK20_VCXO_C_P") (class "Default")
      (node (ref "C410") (pin "2") (pinfunction "2_2") (pintype "passive"))
      (node (ref "IC8") (pin "70") (pinfunction "IP14_70") (pintype "input"))
    )
    (net (code "16") (name "/CLK_SCL") (class "Default")
      (node (ref "IC56") (pin "6") (pinfunction "SCL2_6") (pintype "bidirectional"))
      (node (ref "R137") (pin "2") (pinfunction "2_2") (pintype "passive"))
      (node (ref "R313") (pin "1") (pinfunction "1_1") (pintype "passive"))
    )
    (net (code "17") (name "/CLK_SCL_R") (class "Default")
      (node (ref "IC8") (pin "76") (pinfunction "SCL/SCK_76") (pintype "input"))
      (node (ref "R137") (pin "1") (pinfunction "1_1") (pintype "passive"))
      (node (ref "R68") (pin "1") (pinfunction "1_1") (pintype "passive"))
    )
    (net (code "18") (name "/CLK_SDA") (class "Default")
      (node (ref "IC56") (pin "5") (pinfunction "SDA2_5") (pintype "bidirectional"))
      (node (ref "R136") (pin "2") (pinfunction "2_2") (pintype "passive"))
      (node (ref "R314") (pin "1") (pinfunction "1_1") (pintype "passive"))
    )
    (net (code "19") (name "/CLK_SDA_R") (class "Default")
      (node (ref "IC8") (pin "75") (pinfunction "SDA/SDO_75") (pintype "bidirectional"))
      (node (ref "R136") (pin "1") (pinfunction "1_1") (pintype "passive"))
      (node (ref "R67") (pin "1") (pinfunction "1_1") (pintype "passive"))
    )
    (net (code "20") (name "/CLK_UPDATEn") (class "Default")
      (node (ref "IC41") (pin "15") (pinfunction "B7_15") (pintype "bidirectional"))
      (node (ref "R140") (pin "2") (pinfunction "2_2") (pintype "passive"))
    )
    (net (code "21") (name "/FCLKA_C_N") (class "Default")
      (node (ref "C395") (pin "2") (pinfunction "2_2") (pintype "passive"))
      (node (ref "IC8") (pin "53") (pinfunction "IN8_53") (pintype "input"))
    )
    (net (code "22") (name "/FCLKA_C_P") (class "Default")
      (node (ref "C393") (pin "2") (pinfunction "2_2") (pintype "passive"))
      (node (ref "IC8") (pin "52") (pinfunction "IP8_52") (pintype "input"))
    )
    (net (code "23") (name "/FCLKA_N") (class "Default")
      (node (ref "C395") (pin "1") (pinfunction "1_1") (pintype "passive"))
    )
    (net (code "24") (name "/FCLKA_P") (class "Default")
      (node (ref "C393") (pin "1") (pinfunction "1_1") (pintype "passive"))
    )
    (net (code "25") (name "/FIN1_CLK2_N") (class "Default")
      (node (ref "IC8") (pin "87") (pinfunction "ON11_87") (pintype "output"))
    )
    (net (code "26") (name "/FIN1_CLK2_P") (class "Default")
      (node (ref "IC8") (pin "86") (pinfunction "OP11_86") (pintype "output"))
    )
    (net (code "27") (name "/FIN1_CLK3_N") (class "Default")
      (node (ref "IC8") (pin "84") (pinfunction "ON10_84") (pintype "output"))
    )
    (net (code "28") (name "/FIN1_CLK3_P") (class "Default")
      (node (ref "IC8") (pin "83") (pinfunction "OP10_83") (pintype "output"))
    )
    (net (code "29") (name "/FIN2_CLK2_N") (class "Default")
      (node (ref "IC8") (pin "96") (pinfunction "ON14_96") (pintype "output"))
    )
    (net (code "30") (name "/FIN2_CLK2_P") (class "Default")
      (node (ref "IC8") (pin "95") (pinfunction "OP14_95") (pintype "output"))
    )
    (net (code "31") (name "/FIN2_CLK3_N") (class "Default")
      (node (ref "IC8") (pin "99") (pinfunction "ON15_99") (pintype "output"))
    )
    (net (code "32") (name "/FIN2_CLK3_P") (class "Default")
      (node (ref "IC8") (pin "98") (pinfunction "OP15_98") (pintype "output"))
    )
    (net (code "33") (name "/FMC1_CLK0_M2C_C_N") (class "Default")
      (node (ref "C485") (pin "2") (pinfunction "2_2") (pintype "passive"))
      (node (ref "IC8") (pin "62") (pinfunction "IN11_62") (pintype "input"))
    )
    (net (code "34") (name "/FMC1_CLK0_M2C_C_P") (class "Default")
      (node (ref "C483") (pin "2") (pinfunction "2_2") (pintype "passive"))
      (node (ref "IC8") (pin "61") (pinfunction "IP11_61") (pintype "input"))
    )
    (net (code "35") (name "/FMC1_CLK0_M2C_N") (class "Default")
      (node (ref "C485") (pin "1") (pinfunction "1_1") (pintype "passive"))
    )
    (net (code "36") (name "/FMC1_CLK0_M2C_P") (class "Default")
      (node (ref "C483") (pin "1") (pinfunction "1_1") (pintype "passive"))
    )
    (net (code "37") (name "/FMC1_CLK1_M2C_C_N") (class "Default")
      (node (ref "C489") (pin "2") (pinfunction "2_2") (pintype "passive"))
      (node (ref "IC8") (pin "59") (pinfunction "IN10_59") (pintype "input"))
    )
    (net (code "38") (name "/FMC1_CLK1_M2C_C_P") (class "Default")
      (node (ref "C487") (pin "2") (pinfunction "2_2") (pintype "passive"))
      (node (ref "IC8") (pin "58") (pinfunction "IP10_58") (pintype "input"))
    )
    (net (code "39") (name "/FMC1_CLK1_M2C_N") (class "Default")
      (node (ref "C489") (pin "1") (pinfunction "1_1") (pintype "passive"))
    )
    (net (code "40") (name "/FMC1_CLK1_M2C_P") (class "Default")
      (node (ref "C487") (pin "1") (pinfunction "1_1") (pintype "passive"))
    )
    (net (code "41") (name "/FMC1_CLK2_BIDIR_C_N") (class "Default")
      (node (ref "C493") (pin "2") (pinfunction "2_2") (pintype "passive"))
      (node (ref "IC8") (pin "65") (pinfunction "IN12_65") (pintype "input"))
    )
    (net (code "42") (name "/FMC1_CLK2_BIDIR_C_P") (class "Default")
      (node (ref "C491") (pin "2") (pinfunction "2_2") (pintype "passive"))
      (node (ref "IC8") (pin "64") (pinfunction "IP12_64") (pintype "input"))
    )
    (net (code "43") (name "/FMC1_CLK2_BIDIR_N") (class "Default")
      (node (ref "C493") (pin "1") (pinfunction "1_1") (pintype "passive"))
    )
    (net (code "44") (name "/FMC1_CLK2_BIDIR_P") (class "Default")
      (node (ref "C491") (pin "1") (pinfunction "1_1") (pintype "passive"))
    )
    (net (code "45") (name "/FMC1_CLK3_BIDIR_C_N") (class "Default")
      (node (ref "C497") (pin "2") (pinfunction "2_2") (pintype "passive"))
      (node (ref "IC8") (pin "56") (pinfunction "IN9_56") (pintype "input"))
    )
    (net (code "46") (name "/FMC1_CLK3_BIDIR_C_P") (class "Default")
      (node (ref "C495") (pin "2") (pinfunction "2_2") (pintype "passive"))
      (node (ref "IC8") (pin "55") (pinfunction "IP9_55") (pintype "input"))
    )
    (net (code "47") (name "/FMC1_CLK3_BIDIR_N") (class "Default")
      (node (ref "C497") (pin "1") (pinfunction "1_1") (pintype "passive"))
    )
    (net (code "48") (name "/FMC1_CLK3_BIDIR_P") (class "Default")
      (node (ref "C495") (pin "1") (pinfunction "1_1") (pintype "passive"))
    )
    (net (code "51") (name "/FMC2_CLK0_M2C_C_N") (class "Default")
      (node (ref "C501") (pin "2") (pinfunction "2_2") (pintype "passive"))
      (node (ref "IC8") (pin "9") (pinfunction "IN2_9") (pintype "input"))
    )
    (net (code "52") (name "/FMC2_CLK0_M2C_C_P") (class "Default")
      (node (ref "C499") (pin "2") (pinfunction "2_2") (pintype "passive"))
      (node (ref "IC8") (pin "8") (pinfunction "IP2_8") (pintype "input"))
    )
    (net (code "53") (name "/FMC2_CLK0_M2C_N") (class "Default")
      (node (ref "C501") (pin "1") (pinfunction "1_1") (pintype "passive"))
    )
    (net (code "54") (name "/FMC2_CLK0_M2C_P") (class "Default")
      (node (ref "C499") (pin "1") (pinfunction "1_1") (pintype "passive"))
    )
    (net (code "55") (name "/FMC2_CLK1_M2C_C_N") (class "Default")
      (node (ref "C505") (pin "2") (pinfunction "2_2") (pintype "passive"))
      (node (ref "IC8") (pin "6") (pinfunction "IN1_6") (pintype "input"))
    )
    (net (code "56") (name "/FMC2_CLK1_M2C_C_P") (class "Default")
      (node (ref "C503") (pin "2") (pinfunction "2_2") (pintype "passive"))
      (node (ref "IC8") (pin "5") (pinfunction "IP1_5") (pintype "input"))
    )
    (net (code "57") (name "/FMC2_CLK1_M2C_N") (class "Default")
      (node (ref "C505") (pin "1") (pinfunction "1_1") (pintype "passive"))
    )
    (net (code "58") (name "/FMC2_CLK1_M2C_P") (class "Default")
      (node (ref "C503") (pin "1") (pinfunction "1_1") (pintype "passive"))
    )
    (net (code "59") (name "/FMC2_CLK2_BIDIR_C_N") (class "Default")
      (node (ref "C509") (pin "2") (pinfunction "2_2") (pintype "passive"))
      (node (ref "IC8") (pin "12") (pinfunction "IN3_12") (pintype "input"))
    )
    (net (code "60") (name "/FMC2_CLK2_BIDIR_C_P") (class "Default")
      (node (ref "C507") (pin "2") (pinfunction "2_2") (pintype "passive"))
      (node (ref "IC8") (pin "11") (pinfunction "IP3_11") (pintype "input"))
    )
    (net (code "61") (name "/FMC2_CLK2_BIDIR_N") (class "Default")
      (node (ref "C509") (pin "1") (pinfunction "1_1") (pintype "passive"))
    )
    (net (code "62") (name "/FMC2_CLK2_BIDIR_P") (class "Default")
      (node (ref "C507") (pin "1") (pinfunction "1_1") (pintype "passive"))
    )
    (net (code "63") (name "/FMC2_CLK3_BIDIR_C_N") (class "Default")
      (node (ref "C513") (pin "2") (pinfunction "2_2") (pintype "passive"))
      (node (ref "IC8") (pin "3") (pinfunction "IN0_3") (pintype "input"))
    )
    (net (code "64") (name "/FMC2_CLK3_BIDIR_C_P") (class "Default")
      (node (ref "C511") (pin "2") (pinfunction "2_2") (pintype "passive"))
      (node (ref "IC8") (pin "2") (pinfunction "IP0_2") (pintype "input"))
    )
    (net (code "65") (name "/FMC2_CLK3_BIDIR_N") (class "Default")
      (node (ref "C513") (pin "1") (pinfunction "1_1") (pintype "passive"))
    )
    (net (code "66") (name "/FMC2_CLK3_BIDIR_P") (class "Default")
      (node (ref "C511") (pin "1") (pinfunction "1_1") (pintype "passive"))
    )
    (net (code "69") (name "/FP2_CLK1_C_N") (class "Default")
      (node (ref "IC8") (pin "49") (pinfunction "ON7_49") (pintype "output"))
    )
    (net (code "70") (name "/FP2_CLK1_C_P") (class "Default")
      (node (ref "IC8") (pin "48") (pinfunction "OP7_48") (pintype "output"))
    )
    (net (code "71") (name "/FP2_CLK2_C_N") (class "Default")
      (node (ref "IC8") (pin "43") (pinfunction "ON5_43") (pintype "output"))
    )
    (net (code "72") (name "/FP2_CLK2_C_P") (class "Default")
      (node (ref "IC8") (pin "42") (pinfunction "OP5_42") (pintype "output"))
    )
    (net (code "73") (name "/FPGA_CLK1_C_N") (class "Default")
      (node (ref "C396") (pin "1") (pinfunction "1_1") (pintype "passive"))
      (node (ref "IC8") (pin "40") (pinfunction "ON4_40") (pintype "output"))
    )
    (net (code "74") (name "/FPGA_CLK1_C_P") (class "Default")
      (node (ref "C394") (pin "1") (pinfunction "1_1") (pintype "passive"))
      (node (ref "IC8") (pin "39") (pinfunction "OP4_39") (pintype "output"))
    )
    (net (code "75") (name "/FPGA_CLK1_N") (class "Default")
      (node (ref "C396") (pin "2") (pinfunction "2_2") (pintype "passive"))
    )
    (net (code "76") (name "/FPGA_CLK1_P") (class "Default")
      (node (ref "C394") (pin "2") (pinfunction "2_2") (pintype "passive"))
    )
    (net (code "77") (name "/GND_R") (class "Default")
      (node (ref "IC8") (pin "26") (pinfunction "*I2C/SPI_26") (pintype "input"))
      (node (ref "R146") (pin "1") (pinfunction "1_1") (pintype "passive"))
    )
    (net (code "78") (name "/LINK01_CLK_N") (class "Default")
      (node (ref "IC8") (pin "46") (pinfunction "ON6_46") (pintype "output"))
    )
    (net (code "79") (name "/LINK01_CLK_P") (class "Default")
      (node (ref "IC8") (pin "45") (pinfunction "OP6_45") (pintype "output"))
    )
    (net (code "80") (name "/LINK23_CLK_N") (class "Default")
      (node (ref "IC8") (pin "81") (pinfunction "ON9_81") (pintype "output"))
    )
    (net (code "81") (name "/LINK23_CLK_P") (class "Default")
      (node (ref "IC8") (pin "80") (pinfunction "OP9_80") (pintype "output"))
    )
    (net (code "82") (name "/OP15C_C_N") (class "Default")
      (node (ref "IC8") (pin "93") (pinfunction "ON13_93") (pintype "output"))
      (node (ref "J11") (pin "1") (pintype "passive"))
    )
    (net (code "83") (name "/OP15C_C_P") (class "Default")
      (node (ref "IC8") (pin "92") (pinfunction "OP13_92") (pintype "output"))
      (node (ref "J7") (pin "1") (pintype "passive"))
    )
    (net (code "84") (name "/P3V3_R0") (class "Default")
      (node (ref "IC8") (pin "50") (pinfunction "ADDR1/SDI_50") (pintype "input"))
      (node (ref "R141") (pin "1") (pinfunction "1_1") (pintype "passive"))
    )
    (net (code "85") (name "/P3V3_R1") (class "Default")
      (node (ref "IC8") (pin "51") (pinfunction "ADDR0/*CS_51") (pintype "input"))
      (node (ref "R145") (pin "1") (pinfunction "1_1") (pintype "passive"))
    )
    (net (code "86") (name "/PCIE_CLK1_C_N") (class "Default")
      (node (ref "IC8") (pin "78") (pinfunction "ON8_78") (pintype "output"))
    )
    (net (code "87") (name "/PCIE_CLK1_C_P") (class "Default")
      (node (ref "IC8") (pin "77") (pinfunction "OP8_77") (pintype "output"))
    )
    (net (code "88") (name "/PLL_DAC1_SYNC_N") (class "Default")
      (node (ref "IC41") (pin "21") (pinfunction "B1_21") (pintype "bidirectional"))
    )
    (net (code "89") (name "/PLL_DAC2_SYNC_N") (class "Default")
      (node (ref "IC41") (pin "19") (pinfunction "B3_19") (pintype "bidirectional"))
    )
    (net (code "90") (name "/PLL_DAC_DIN") (class "Default")
      (node (ref "IC41") (pin "18") (pinfunction "B4_18") (pintype "bidirectional"))
    )
    (net (code "91") (name "/PLL_DAC_SCLK") (class "Default")
      (node (ref "IC41") (pin "20") (pinfunction "B2_20") (pintype "bidirectional"))
    )
    (net (code "92") (name "/PLL_VADJ2_DAC1_SYNC_N") (class "Default")
      (node (ref "IC41") (pin "5") (pinfunction "A3_5") (pintype "bidirectional"))
    )
    (net (code "93") (name "/PLL_VADJ2_DAC2_SYNC_N") (class "Default")
      (node (ref "IC41") (pin "3") (pinfunction "A1_3") (pintype "bidirectional"))
    )
    (net (code "94") (name "/PLL_VADJ2_DAC_DIN") (class "Default")
      (node (ref "IC41") (pin "6") (pinfunction "A4_6") (pintype "bidirectional"))
    )
    (net (code "95") (name "/PLL_VADJ2_DAC_SCLK") (class "Default")
      (node (ref "IC41") (pin "4") (pinfunction "A2_4") (pintype "bidirectional"))
    )
    (net (code "96") (name "/RESETn") (class "Default")
      (node (ref "IC8") (pin "1") (pinfunction "RESET_1") (pintype "input"))
    )
    (net (code "97") (name "/RTM_SYNC_CLK_N") (class "Default")
      (node (ref "C814") (pin "2") (pinfunction "2_2") (pintype "passive"))
    )
    (net (code "98") (name "/RTM_SYNC_CLK_P") (class "Default")
      (node (ref "C813") (pin "2") (pinfunction "2_2") (pintype "passive"))
    )
    (net (code "99") (name "/SI57X_CLK_C_N") (class "Default")
      (node (ref "C403") (pin "2") (pinfunction "2_2") (pintype "passive"))
      (node (ref "IC8") (pin "73") (pinfunction "IP15_73") (pintype "input"))
    )
    (net (code "100") (name "/SI57X_CLK_C_P") (class "Default")
      (node (ref "C401") (pin "2") (pinfunction "2_2") (pintype "passive"))
      (node (ref "IC8") (pin "74") (pinfunction "IN15_74") (pintype "input"))
    )
    (net (code "101") (name "/SI57X_CLK_N") (class "Default")
      (node (ref "C403") (pin "1") (pinfunction "1_1") (pintype "passive"))
    )
    (net (code "102") (name "/SI57X_CLK_P") (class "Default")
      (node (ref "C401") (pin "1") (pinfunction "1_1") (pintype "passive"))
    )
    (net (code "103") (name "/SI57X_OE") (class "Default")
      (node (ref "IC41") (pin "17") (pinfunction "B5_17") (pintype "bidirectional"))
    )
    (net (code "104") (name "/SI57X_SCL") (class "Default")
      (node (ref "IC42") (pin "7") (pinfunction "SCLB_7") (pintype "bidirectional"))
      (node (ref "R68") (pin "2") (pinfunction "2_2") (pintype "passive"))
    )
    (net (code "105") (name "/SI57X_SDA") (class "Default")
      (node (ref "IC42") (pin "6") (pinfunction "SDAB_6") (pintype "bidirectional"))
      (node (ref "R67") (pin "2") (pinfunction "2_2") (pintype "passive"))
    )
    (net (code "106") (name "/SI57X_TUNE") (class "Default")
      (node (ref "IC41") (pin "16") (pinfunction "B6_16") (pintype "bidirectional"))
    )
    (net (code "107") (name "/TCLKA_CIN_N") (class "Default")
      (node (ref "C458") (pin "2") (pinfunction "2_2") (pintype "passive"))
      (node (ref "IC8") (pin "17") (pinfunction "IP5_17") (pintype "input"))
    )
    (net (code "108") (name "/TCLKA_CIN_P") (class "Default")
      (node (ref "C414") (pin "2") (pinfunction "2_2") (pintype "passive"))
      (node (ref "IC8") (pin "18") (pinfunction "IN5_18") (pintype "input"))
    )
    (net (code "109") (name "/TCLKA_COUT_N") (class "Default")
      (node (ref "C482") (pin "1") (pinfunction "1_1") (pintype "passive"))
      (node (ref "IC8") (pin "34") (pinfunction "ON2_34") (pintype "output"))
    )
    (net (code "110") (name "/TCLKA_COUT_P") (class "Default")
      (node (ref "C480") (pin "1") (pinfunction "1_1") (pintype "passive"))
      (node (ref "IC8") (pin "33") (pinfunction "OP2_33") (pintype "output"))
    )
    (net (code "111") (name "/TCLKA_N") (class "Default")
      (node (ref "C458") (pin "1") (pinfunction "1_1") (pintype "passive"))
      (node (ref "C482") (pin "2") (pinfunction "2_2") (pintype "passive"))
    )
    (net (code "112") (name "/TCLKA_P") (class "Default")
      (node (ref "C414") (pin "1") (pinfunction "1_1") (pintype "passive"))
      (node (ref "C480") (pin "2") (pinfunction "2_2") (pintype "passive"))
    )
    (net (code "113") (name "/TCLKB_CIN_N") (class "Default")
      (node (ref "C462") (pin "2") (pinfunction "2_2") (pintype "passive"))
      (node (ref "IC8") (pin "14") (pinfunction "IP4_14") (pintype "input"))
    )
    (net (code "114") (name "/TCLKB_CIN_P") (class "Default")
      (node (ref "C460") (pin "2") (pinfunction "2_2") (pintype "passive"))
      (node (ref "IC8") (pin "15") (pinfunction "IN4_15") (pintype "input"))
    )
    (net (code "115") (name "/TCLKB_COUT_N") (class "Default")
      (node (ref "C486") (pin "1") (pinfunction "1_1") (pintype "passive"))
      (node (ref "IC8") (pin "37") (pinfunction "ON3_37") (pintype "output"))
    )
    (net (code "116") (name "/TCLKB_COUT_P") (class "Default")
      (node (ref "C484") (pin "1") (pinfunction "1_1") (pintype "passive"))
      (node (ref "IC8") (pin "36") (pinfunction "OP3_36") (pintype "output"))
    )
    (net (code "117") (name "/TCLKB_N") (class "Default")
      (node (ref "C462") (pin "1") (pinfunction "1_1") (pintype "passive"))
      (node (ref "C486") (pin "2") (pinfunction "2_2") (pintype "passive"))
    )
    (net (code "118") (name "/TCLKB_P") (class "Default")
      (node (ref "C460") (pin "1") (pinfunction "1_1") (pintype "passive"))
      (node (ref "C484") (pin "2") (pinfunction "2_2") (pintype "passive"))
    )
    (net (code "119") (name "/TCLKC_CIN_N") (class "Default")
      (node (ref "C477") (pin "2") (pinfunction "2_2") (pintype "passive"))
      (node (ref "IC8") (pin "20") (pinfunction "IP6_20") (pintype "input"))
    )
    (net (code "120") (name "/TCLKC_CIN_P") (class "Default")
      (node (ref "C464") (pin "2") (pinfunction "2_2") (pintype "passive"))
      (node (ref "IC8") (pin "21") (pinfunction "IN6_21") (pintype "input"))
    )
    (net (code "121") (name "/TCLKC_COUT_N") (class "Default")
      (node (ref "C490") (pin "1") (pinfunction "1_1") (pintype "passive"))
      (node (ref "IC8") (pin "31") (pinfunction "ON1_31") (pintype "output"))
    )
    (net (code "122") (name "/TCLKC_COUT_P") (class "Default")
      (node (ref "C488") (pin "1") (pinfunction "1_1") (pintype "passive"))
      (node (ref "IC8") (pin "30") (pinfunction "OP1_30") (pintype "output"))
    )
    (net (code "123") (name "/TCLKC_N") (class "Default")
      (node (ref "C477") (pin "1") (pinfunction "1_1") (pintype "passive"))
      (node (ref "C490") (pin "2") (pinfunction "2_2") (pintype "passive"))
    )
    (net (code "124") (name "/TCLKC_P") (class "Default")
      (node (ref "C464") (pin "1") (pinfunction "1_1") (pintype "passive"))
      (node (ref "C488") (pin "2") (pinfunction "2_2") (pintype "passive"))
    )
    (net (code "125") (name "/TCLKD_CIN_N") (class "Default")
      (node (ref "C481") (pin "2") (pinfunction "2_2") (pintype "passive"))
      (node (ref "IC8") (pin "23") (pinfunction "IP7_23") (pintype "input"))
    )
    (net (code "126") (name "/TCLKD_CIN_P") (class "Default")
      (node (ref "C479") (pin "2") (pinfunction "2_2") (pintype "passive"))
      (node (ref "IC8") (pin "24") (pinfunction "IN7_24") (pintype "input"))
    )
    (net (code "127") (name "/TCLKD_COUT_N") (class "Default")
      (node (ref "C494") (pin "1") (pinfunction "1_1") (pintype "passive"))
      (node (ref "IC8") (pin "28") (pinfunction "ON0_28") (pintype "output"))
    )
    (net (code "128") (name "/TCLKD_COUT_P") (class "Default")
      (node (ref "C492") (pin "1") (pinfunction "1_1") (pintype "passive"))
      (node (ref "IC8") (pin "27") (pinfunction "OP0_27") (pintype "output"))
    )
    (net (code "129") (name "/TCLKD_N") (class "Default")
      (node (ref "C481") (pin "1") (pinfunction "1_1") (pintype "passive"))
      (node (ref "C494") (pin "2") (pinfunction "2_2") (pintype "passive"))
    )
    (net (code "130") (name "/TCLKD_P") (class "Default")
      (node (ref "C479") (pin "1") (pinfunction "1_1") (pintype "passive"))
      (node (ref "C492") (pin "2") (pinfunction "2_2") (pintype "passive"))
    )
    (net (code "132") (name "/UPDATEn") (class "Default")
      (node (ref "R139") (pin "2") (pinfunction "2_2") (pintype "passive"))
    )
    (net (code "133") (name "/UPD_R") (class "Default")
      (node (ref "IC8") (pin "25") (pinfunction "*UPDATE_25") (pintype "passive"))
      (node (ref "R139") (pin "1") (pinfunction "1_1") (pintype "passive"))
      (node (ref "R140") (pin "1") (pinfunction "1_1") (pintype "passive"))
    )
    (net (code "134") (name "/VADJ2_CLK_UPDATEn") (class "Default")
      (node (ref "IC41") (pin "9") (pinfunction "A7_9") (pintype "bidirectional"))
    )
    (net (code "135") (name "/VADJ2_SI57X_OE") (class "Default")
      (node (ref "IC41") (pin "7") (pinfunction "A5_7") (pintype "bidirectional"))
    )
    (net (code "136") (name "/VADJ2_SI57X_SCL") (class "Default")
      (node (ref "IC42") (pin "2") (pinfunction "SCLA_2") (pintype "bidirectional"))
      (node (ref "R271") (pin "2") (pinfunction "2_2") (pintype "passive"))
    )
    (net (code "137") (name "/VADJ2_SI57X_SDA") (class "Default")
      (node (ref "IC42") (pin "3") (pinfunction "SDAA_3") (pintype "bidirectional"))
      (node (ref "R214") (pin "2") (pinfunction "2_2") (pintype "passive"))
    )
    (net (code "138") (name "/VADJ2_SI57X_TUNE") (class "Default")
      (node (ref "IC41") (pin "8") (pinfunction "A6_8") (pintype "bidirectional"))
    )
    (net (code "139") (name "/VTTI") (class "Default")
      (node (ref "C571") (pin "1") (pinfunction "1_1") (pintype "passive"))
      (node (ref "C572") (pin "1") (pinfunction "1_1") (pintype "passive"))
      (node (ref "C573") (pin "1") (pinfunction "1_1") (pintype "passive"))
      (node (ref "C574") (pin "1") (pinfunction "1_1") (pintype "passive"))
      (node (ref "IC8") (pin "19") (pinfunction "VTTIW_19") (pintype "passive"))
      (node (ref "IC8") (pin "57") (pinfunction "VTTIE_57") (pintype "passive"))
      (node (ref "IC8") (pin "69") (pinfunction "VTTIE_69") (pintype "passive"))
      (node (ref "IC8") (pin "7") (pinfunction "VTTIW_7") (pintype "passive"))
      (node (ref "L19") (pin "1") (pinfunction "1_1") (pintype "passive"))
    )
    (net (code "140") (name "/VTTO") (class "Default")
      (node (ref "C567") (pin "2") (pinfunction "2_2") (pintype "passive"))
      (node (ref "C568") (pin "2") (pinfunction "2_2") (pintype "passive"))
      (node (ref "C569") (pin "2") (pinfunction "2_2") (pintype "passive"))
      (node (ref "C570") (pin "2") (pinfunction "2_2") (pintype "passive"))
      (node (ref "IC8") (pin "32") (pinfunction "VTTOS_32") (pintype "passive"))
      (node (ref "IC8") (pin "44") (pinfunction "VTTOS_44") (pintype "passive"))
      (node (ref "IC8") (pin "82") (pinfunction "VTTON_82") (pintype "passive"))
      (node (ref "IC8") (pin "94") (pinfunction "VTTON_94") (pintype "passive"))
      (node (ref "L18") (pin "1") (pinfunction "1_1") (pintype "passive"))
    )
    (net (code "141") (name "/WR_PLL_CLK1_C_N") (class "Default")
      (node (ref "C399") (pin "2") (pinfunction "2_2") (pintype "passive"))
      (node (ref "IC8") (pin "68") (pinfunction "IN13_68") (pintype "input"))
    )
    (net (code "142") (name "/WR_PLL_CLK1_C_P") (class "Default")
      (node (ref "C397") (pin "2") (pinfunction "2_2") (pintype "passive"))
      (node (ref "IC8") (pin "67") (pinfunction "IP13_67") (pintype "input"))
    )
    (net (code "143") (name "/WR_PLL_CLK1_N") (class "Default")
      (node (ref "C399") (pin "1") (pinfunction "1_1") (pintype "passive"))
    )
    (net (code "144") (name "/WR_PLL_CLK1_P") (class "Default")
      (node (ref "C397") (pin "1") (pinfunction "1_1") (pintype "passive"))
    )
    (net (code "152") (name "GND") (class "Default")
      (node (ref "C128") (pin "1") (pinfunction "1_1") (pintype "passive"))
      (node (ref "C389") (pin "1") (pinfunction "1_1") (pintype "passive"))
      (node (ref "C391") (pin "1") (pinfunction "1_1") (pintype "passive"))
      (node (ref "C408") (pin "1") (pinfunction "1_1") (pintype "passive"))
      (node (ref "C412") (pin "1") (pinfunction "1_1") (pintype "passive"))
      (node (ref "C454") (pin "1") (pinfunction "1_1") (pintype "passive"))
      (node (ref "C515") (pin "1") (pinfunction "1_1") (pintype "passive"))
      (node (ref "C516") (pin "1") (pinfunction "1_1") (pintype "passive"))
      (node (ref "C517") (pin "1") (pinfunction "1_1") (pintype "passive"))
      (node (ref "C518") (pin "1") (pinfunction "1_1") (pintype "passive"))
      (node (ref "C519") (pin "1") (pinfunction "1_1") (pintype "passive"))
      (node (ref "C520") (pin "1") (pinfunction "1_1") (pintype "passive"))
      (node (ref "C521") (pin "1") (pinfunction "1_1") (pintype "passive"))
      (node (ref "C522") (pin "1") (pinfunction "1_1") (pintype "passive"))
      (node (ref "C523") (pin "1") (pinfunction "1_1") (pintype "passive"))
      (node (ref "C524") (pin "1") (pinfunction "1_1") (pintype "passive"))
      (node (ref "C567") (pin "1") (pinfunction "1_1") (pintype "passive"))
      (node (ref "C568") (pin "1") (pinfunction "1_1") (pintype "passive"))
      (node (ref "C569") (pin "1") (pinfunction "1_1") (pintype "passive"))
      (node (ref "C570") (pin "1") (pinfunction "1_1") (pintype "passive"))
      (node (ref "C571") (pin "2") (pinfunction "2_2") (pintype "passive"))
      (node (ref "C572") (pin "2") (pinfunction "2_2") (pintype "passive"))
      (node (ref "C573") (pin "2") (pinfunction "2_2") (pintype "passive"))
      (node (ref "C574") (pin "2") (pinfunction "2_2") (pintype "passive"))
      (node (ref "C762") (pin "2") (pinfunction "2_2") (pintype "passive"))
      (node (ref "C766") (pin "2") (pinfunction "2_2") (pintype "passive"))
      (node (ref "CC524") (pin "1") (pinfunction "1_1") (pintype "passive"))
      (node (ref "IC41") (pin "10") (pinfunction "A8_10") (pintype "bidirectional"))
      (node (ref "IC41") (pin "11") (pinfunction "GND_11") (pintype "power_in"))
      (node (ref "IC41") (pin "12") (pinfunction "GND_12") (pintype "power_in"))
      (node (ref "IC41") (pin "13") (pinfunction "GND_13") (pintype "power_in"))
      (node (ref "IC41") (pin "22") (pinfunction "~{OE}_22") (pintype "input"))
      (node (ref "IC41") (pin "25") (pinfunction "GND_25") (pintype "power_in"))
      (node (ref "IC42") (pin "4") (pinfunction "GND_4") (pintype "power_in"))
      (node (ref "IC56") (pin "1") (pinfunction "GND_1") (pintype "power_in"))
      (node (ref "IC8") (pin "0") (pinfunction "EP(VEE)_0") (pintype "power_in"))
      (node (ref "IC8") (pin "10") (pinfunction "VEE_10") (pintype "power_in"))
      (node (ref "IC8") (pin "16") (pinfunction "VEE_16") (pintype "power_in"))
      (node (ref "IC8") (pin "29") (pinfunction "VEE_29") (pintype "power_in"))
      (node (ref "IC8") (pin "38") (pinfunction "VEE_38") (pintype "power_in"))
      (node (ref "IC8") (pin "47") (pinfunction "VEE_47") (pintype "power_in"))
      (node (ref "IC8") (pin "60") (pinfunction "VEE_60") (pintype "power_in"))
      (node (ref "IC8") (pin "66") (pinfunction "VEE_66") (pintype "power_in"))
      (node (ref "IC8") (pin "79") (pinfunction "VEE_79") (pintype "power_in"))
      (node (ref "IC8") (pin "88") (pinfunction "VEE_88") (pintype "power_in"))
      (node (ref "IC8") (pin "97") (pinfunction "VEE_97") (pintype "power_in"))
      (node (ref "J11") (pin "2") (pintype "passive"))
      (node (ref "J11") (pin "2a") (pinfunction "GND_2a") (pintype "passive"))
      (node (ref "J7") (pin "2") (pintype "passive"))
      (node (ref "J7") (pin "2a") (pinfunction "GND_2a") (pintype "passive"))
      (node (ref "R146") (pin "2") (pinfunction "2_2") (pintype "passive"))
    )
    (net (code "153") (name "Net-(IC8B-ON12)") (class "Default")
      (node (ref "C814") (pin "1") (pinfunction "1_1") (pintype "passive"))
      (node (ref "IC8") (pin "90") (pinfunction "ON12_90") (pintype "output"))
    )
    (net (code "154") (name "Net-(IC8B-OP12)") (class "Default")
      (node (ref "C813") (pin "1") (pinfunction "1_1") (pintype "passive"))
      (node (ref "IC8") (pin "89") (pinfunction "OP12_89") (pintype "output"))
    )
    (net (code "155") (name "Net-(IC56-EN)") (class "Default")
      (node (ref "C762") (pin "1") (pinfunction "1_1") (pintype "passive"))
      (node (ref "IC56") (pin "7") (pinfunction "VREF2_7") (pintype "input"))
      (node (ref "IC56") (pin "8") (pinfunction "EN_8") (pintype "input"))
      (node (ref "R52") (pin "2") (pinfunction "2_2") (pintype "passive"))
    )
    (net (code "156") (name "P3V3") (class "Default")
      (node (ref "C389") (pin "2") (pinfunction "2_2") (pintype "passive"))
      (node (ref "C391") (pin "2") (pinfunction "2_2") (pintype "passive"))
      (node (ref "IC41") (pin "23") (pinfunction "VCCB_23") (pintype "power_in"))
      (node (ref "IC41") (pin "24") (pinfunction "VCCB_24") (pintype "power_in"))
      (node (ref "IC42") (pin "5") (pinfunction "EN_5") (pintype "input"))
      (node (ref "IC42") (pin "8") (pinfunction "Vccb_8") (pintype "power_in"))
      (node (ref "L11") (pin "1") (pintype "passive"))
      (node (ref "R313") (pin "2") (pinfunction "2_2") (pintype "passive"))
      (node (ref "R314") (pin "2") (pinfunction "2_2") (pintype "passive"))
      (node (ref "R52") (pin "1") (pinfunction "1_1") (pintype "passive"))
    )
    (net (code "157") (name "P3V3MP") (class "Default")
      (node (ref "C766") (pin "1") (pinfunction "1_1") (pintype "passive"))
      (node (ref "IC56") (pin "2") (pinfunction "VREF1_2") (pintype "input"))
    )
    (net (code "158") (name "P3V3_CLKSW") (class "Default")
      (node (ref "C454") (pin "2") (pinfunction "2_2") (pintype "passive"))
      (node (ref "C515") (pin "2") (pinfunction "2_2") (pintype "passive"))
      (node (ref "C516") (pin "2") (pinfunction "2_2") (pintype "passive"))
      (node (ref "C517") (pin "2") (pinfunction "2_2") (pintype "passive"))
      (node (ref "C518") (pin "2") (pinfunction "2_2") (pintype "passive"))
      (node (ref "C519") (pin "2") (pinfunction "2_2") (pintype "passive"))
      (node (ref "C520") (pin "2") (pinfunction "2_2") (pintype "passive"))
      (node (ref "C521") (pin "2") (pinfunction "2_2") (pintype "passive"))
      (node (ref "C522") (pin "2") (pinfunction "2_2") (pintype "passive"))
      (node (ref "C523") (pin "2") (pinfunction "2_2") (pintype "passive"))
      (node (ref "C524") (pin "2") (pinfunction "2_2") (pintype "passive"))
      (node (ref "CC524") (pin "2") (pinfunction "2_2") (pintype "passive"))
      (node (ref "IC8") (pin "100") (pinfunction "DVCC_100") (pintype "power_in"))
      (node (ref "IC8") (pin "13") (pinfunction "VCC_13") (pintype "power_in"))
      (node (ref "IC8") (pin "22") (pinfunction "VCC_22") (pintype "power_in"))
      (node (ref "IC8") (pin "35") (pinfunction "VCC_35") (pintype "power_in"))
      (node (ref "IC8") (pin "4") (pinfunction "VCC_4") (pintype "power_in"))
      (node (ref "IC8") (pin "41") (pinfunction "VCC_41") (pintype "power_in"))
      (node (ref "IC8") (pin "54") (pinfunction "VCC_54") (pintype "power_in"))
      (node (ref "IC8") (pin "63") (pinfunction "VCC_63") (pintype "power_in"))
      (node (ref "IC8") (pin "72") (pinfunction "VCC_72") (pintype "power_in"))
      (node (ref "IC8") (pin "85") (pinfunction "VCC_85") (pintype "power_in"))
      (node (ref "IC8") (pin "91") (pinfunction "VCC_91") (pintype "power_in"))
      (node (ref "L11") (pin "2") (pintype "passive"))
      (node (ref "L18") (pin "2") (pinfunction "2_2") (pintype "passive"))
      (node (ref "L19") (pin "2") (pinfunction "2_2") (pintype "passive"))
      (node (ref "R141") (pin "2") (pinfunction "2_2") (pintype "passive"))
      (node (ref "R145") (pin "2") (pinfunction "2_2") (pintype "passive"))
    )
    (net (code "159") (name "PVADJ2") (class "Default")
      (node (ref "C128") (pin "2") (pinfunction "2_2") (pintype "passive"))
      (node (ref "C408") (pin "2") (pinfunction "2_2") (pintype "passive"))
      (node (ref "IC41") (pin "1") (pinfunction "VCCA_1") (pintype "power_in"))
      (node (ref "IC41") (pin "2") (pinfunction "DIR_2") (pintype "input"))
      (node (ref "IC42") (pin "1") (pinfunction "Vcca_1") (pintype "power_in"))
      (node (ref "R214") (pin "1") (pinfunction "1_1") (pintype "passive"))
      (node (ref "R271") (pin "1") (pinfunction "1_1") (pintype "passive"))
    )
    (net (code "160") (name "unconnected-(IC41-B8-Pad14)") (class "Default")
      (node (ref "IC41") (pin "14") (pinfunction "B8_14") (pintype "bidirectional"))
    )
    (net (code "161") (name "unconnected-(IC56-SCL1-Pad3)") (class "Default")
      (node (ref "IC56") (pin "3") (pinfunction "SCL1_3") (pintype "bidirectional"))
    )
    (net (code "162") (name "unconnected-(IC56-SDA1-Pad4)") (class "Default")
      (node (ref "IC56") (pin "4") (pinfunction "SDA1_4") (pintype "bidirectional"))
    )
  )
)
